# H05R1_Frontend_1.net
KiCad netlist of a schematic drawn in Altium Designer
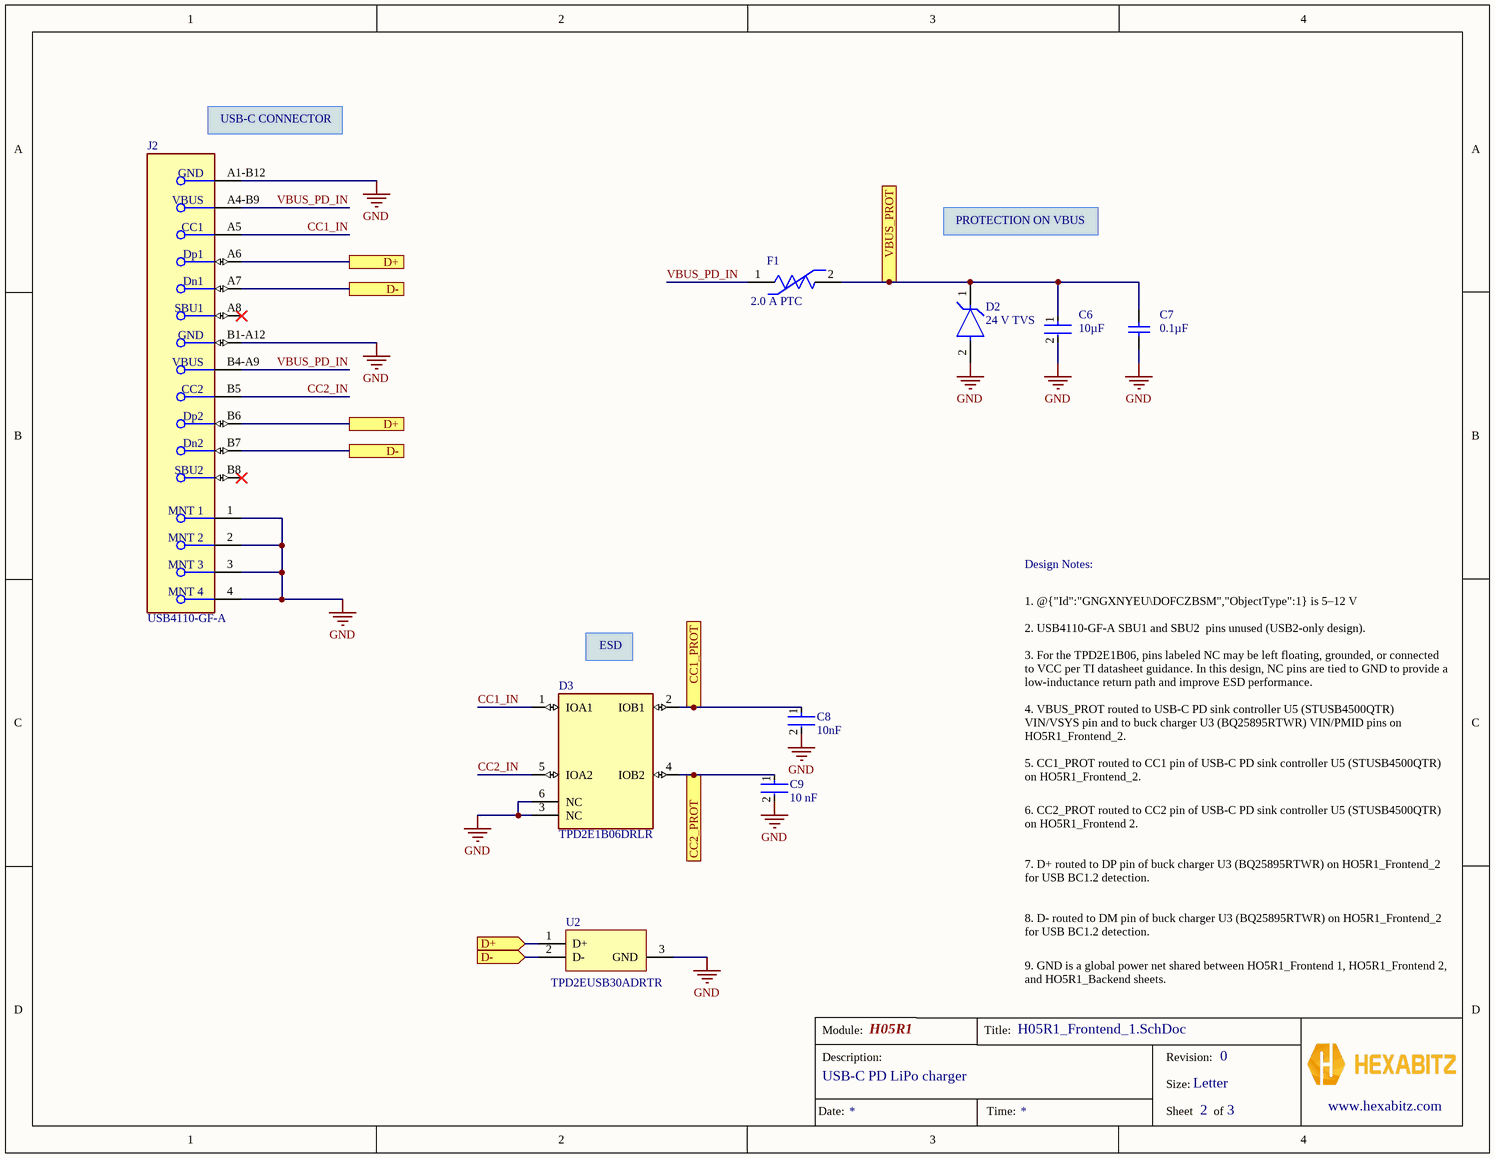
[diagram p0: H05R1_Frontend_1.SchDoc]

(export (version "E")
  (design (tool "Eeschema 10.0.6"))
  (components
    (comp (ref "C6")
      (value "10µF")
      (footprint "FP-GRM32-MFG")
      (description "CAP CER 10UF 50V X7R 1210")
      (fields (field (name "TOLERANCE") "10%") (field (name "MANUFACTURER PART NUMBER") "GRM32ER71H106KA12L"))
      (libsource (lib "Altium Content Vault") (part "11868f565c42a9108669ba33697ecf6"))
    )
    (comp (ref "C7")
      (value "0.1µF")
      (footprint "CAPC1608X90X35ML10T15")
      (description "Chip Capacitor, 0.1 uF, +/- 10%, 50 V, -55 to 125 degC, 0603 (1608 Metric), RoHS, Tape and Reel")
      (fields (field (name "TOLERANCE") "10%") (field (name "VOLTAGE") "50V"))
      (libsource (lib "Altium Content Vault") (part "CAP-NP-2"))
    )
    (comp (ref "C8")
      (value "10nF")
      (footprint "FP-GRM155-0_05-IPC_C")
      (description "Chip Multilayer Ceramic Capacitors for General Purpose, 0402, 10000pF, X7R, 15%, 10%, 50V")
      (fields (field (name "TOLERANCE") "10%") (field (name "VOLTAGE") "25V"))
      (libsource (lib "Altium Content Vault") (part "02cd4be3c70576c341d710602a673aa"))
    )
    (comp (ref "C9")
      (value "10 nF")
      (footprint "FP-GRM155-0_05-IPC_C")
      (description "Chip Multilayer Ceramic Capacitors for General Purpose, 0402, 10000pF, X7R, 15%, 10%, 50V")
      (fields (field (name "TOLERANCE") "10%") (field (name "VOLTAGE") "25V"))
      (libsource (lib "Altium Content Vault") (part "02cd4be3c70576c341d710602a673aa"))
    )
    (comp (ref "D2")
      (value "24 V TVS")
      (footprint "FP-SMBJ-MFG")
      (description "TVS DIODE 24V 38.9V SMB")
      (fields
        (field (name "MPN") "SMBJ24A")
        (field (name "OCTOPART") "https://octopart.com/smbj24a-bourns-12809467")
      )
      (libsource (lib "Altium Content Vault") (part "f813f71cba58e380607f5dd3caf9714"))
    )
    (comp (ref "D3")
      (value "TPD2E1B06DRLR")
      (footprint "FP-DRL0006A-MFG")
      (description "TVS DIODE 5.5V 15V 6SOT")
      (fields
        (field (name "OCTOPART") "https://octopart.com/tpd2e1b06drlr-texas+instruments-30488860")
        (field (name "MANUFACTURER") "Texas Instruments")
      )
      (libsource (lib "Altium Content Vault") (part "f3dc085ebb28d99bc65c213f373c040"))
    )
    (comp (ref "F1")
      (value "2.0 A PTC")
      (footprint "FP-0ZCF0200AF2C-MFG")
      (description "PTC RESET FUSE 24V 2A 2920")
      (fields (field (name "MPN") "0ZCF0200AF2C"))
      (libsource (lib "Altium Content Vault") (part "386f8dcc7afc1e43cc3b665cf7cc17d"))
    )
    (comp (ref "J2")
      (value "USB4110-GF-A")
      (footprint "FP-USB4110-GF-A-MFG")
      (description "CONN USB 2.0 TYPE-C R/A SMT")
      (fields
        (field (name "OCTOPART") "https://octopart.com/usb4110-gf-a-gct-103941985")
        (field (name "MANUFACTURER") "GCT")
      )
      (libsource (lib "Altium Content Vault") (part "e23f2b38bb3c3f98e683ebab9ede730"))
    )
    (comp (ref "U2")
      (value "TPD2EUSB30ADRTR")
      (footprint "DRT0003A")
      (fields
        (field (name "MANUFACTURER") "Texas Instruments")
        (field (name "OCTOPART") "https://octopart.com/tpd2eusb30adrtr-texas+instruments-19659288")
      )
      (libsource (lib "Altium Content Vault") (part "TI-TPD2EUSB30A-SOT_DRT-3"))
    )
  )
  (nets
    (net (code "1") (name "/CC1_IN") (class "Default")
      (node (ref "D3") (pin "1") (pinfunction "IOA1_1") (pintype "bidirectional"))
      (node (ref "J2") (pin "A5") (pinfunction "CC1_A5") (pintype "power_in"))
    )
    (net (code "2") (name "/CC1_PROT") (class "Default")
      (node (ref "C8") (pin "1") (pinfunction "1_1") (pintype "passive"))
      (node (ref "D3") (pin "2") (pinfunction "IOB1_2") (pintype "bidirectional"))
    )
    (net (code "3") (name "/CC2_IN") (class "Default")
      (node (ref "D3") (pin "5") (pinfunction "IOA2_5") (pintype "bidirectional"))
      (node (ref "J2") (pin "B5") (pinfunction "CC2_B5") (pintype "power_in"))
    )
    (net (code "4") (name "/CC2_PROT") (class "Default")
      (node (ref "C9") (pin "1") (pinfunction "1_1") (pintype "passive"))
      (node (ref "D3") (pin "4") (pinfunction "IOB2_4") (pintype "bidirectional"))
    )
    (net (code "5") (name "/D+") (class "Default")
      (node (ref "J2") (pin "A6") (pinfunction "Dp1_A6") (pintype "bidirectional"))
      (node (ref "J2") (pin "B6") (pinfunction "Dp2_B6") (pintype "bidirectional"))
      (node (ref "U2") (pin "1") (pinfunction "D+_1") (pintype "passive"))
    )
    (net (code "6") (name "/D-") (class "Default")
      (node (ref "J2") (pin "A7") (pinfunction "Dn1_A7") (pintype "bidirectional"))
      (node (ref "J2") (pin "B7") (pinfunction "Dn2_B7") (pintype "bidirectional"))
      (node (ref "U2") (pin "2") (pinfunction "D-_2") (pintype "passive"))
    )
    (net (code "7") (name "/VBUS_PD_IN") (class "Default")
      (node (ref "F1") (pin "1") (pinfunction "1_1") (pintype "passive"))
      (node (ref "J2") (pin "A4-B9") (pinfunction "VBUS_A4-B9") (pintype "power_in"))
      (node (ref "J2") (pin "B4-A9") (pinfunction "VBUS_B4-A9") (pintype "power_in"))
    )
    (net (code "8") (name "/VBUS_PROT") (class "Default")
      (node (ref "C6") (pin "1") (pinfunction "1_1") (pintype "passive"))
      (node (ref "C7") (pin "2") (pinfunction "2_2") (pintype "passive"))
      (node (ref "D2") (pin "1") (pinfunction "C_1") (pintype "passive"))
      (node (ref "F1") (pin "2") (pinfunction "2_2") (pintype "passive"))
    )
    (net (code "9") (name "GND") (class "Default")
      (node (ref "C6") (pin "2") (pinfunction "2_2") (pintype "passive"))
      (node (ref "C7") (pin "1") (pinfunction "1_1") (pintype "passive"))
      (node (ref "C8") (pin "2") (pinfunction "2_2") (pintype "passive"))
      (node (ref "C9") (pin "2") (pinfunction "2_2") (pintype "passive"))
      (node (ref "D2") (pin "2") (pinfunction "A_2") (pintype "passive"))
      (node (ref "D3") (pin "3") (pinfunction "NC_3") (pintype "passive"))
      (node (ref "D3") (pin "6") (pinfunction "NC_6") (pintype "passive"))
      (node (ref "J2") (pin "1") (pinfunction "MNT_1_1") (pintype "passive"))
      (node (ref "J2") (pin "2") (pinfunction "MNT_2_2") (pintype "passive"))
      (node (ref "J2") (pin "3") (pinfunction "MNT_3_3") (pintype "passive"))
      (node (ref "J2") (pin "4") (pinfunction "MNT_4_4") (pintype "passive"))
      (node (ref "J2") (pin "A1-B12") (pinfunction "GND_A1-B12") (pintype "passive"))
      (node (ref "J2") (pin "B1-A12") (pinfunction "GND_B1-A12") (pintype "bidirectional"))
      (node (ref "U2") (pin "3") (pinfunction "GND_3") (pintype "power_in"))
    )
    (net (code "10") (name "unconnected-(J2-SBU1-PadA8)") (class "Default")
      (node (ref "J2") (pin "A8") (pinfunction "SBU1_A8") (pintype "bidirectional+no_connect"))
    )
    (net (code "11") (name "unconnected-(J2-SBU2-PadB8)") (class "Default")
      (node (ref "J2") (pin "B8") (pinfunction "SBU2_B8") (pintype "bidirectional+no_connect"))
    )
  )
)
